# JAjchel_schemat.net
KiCad netlist of a schematic drawn in Altium Designer
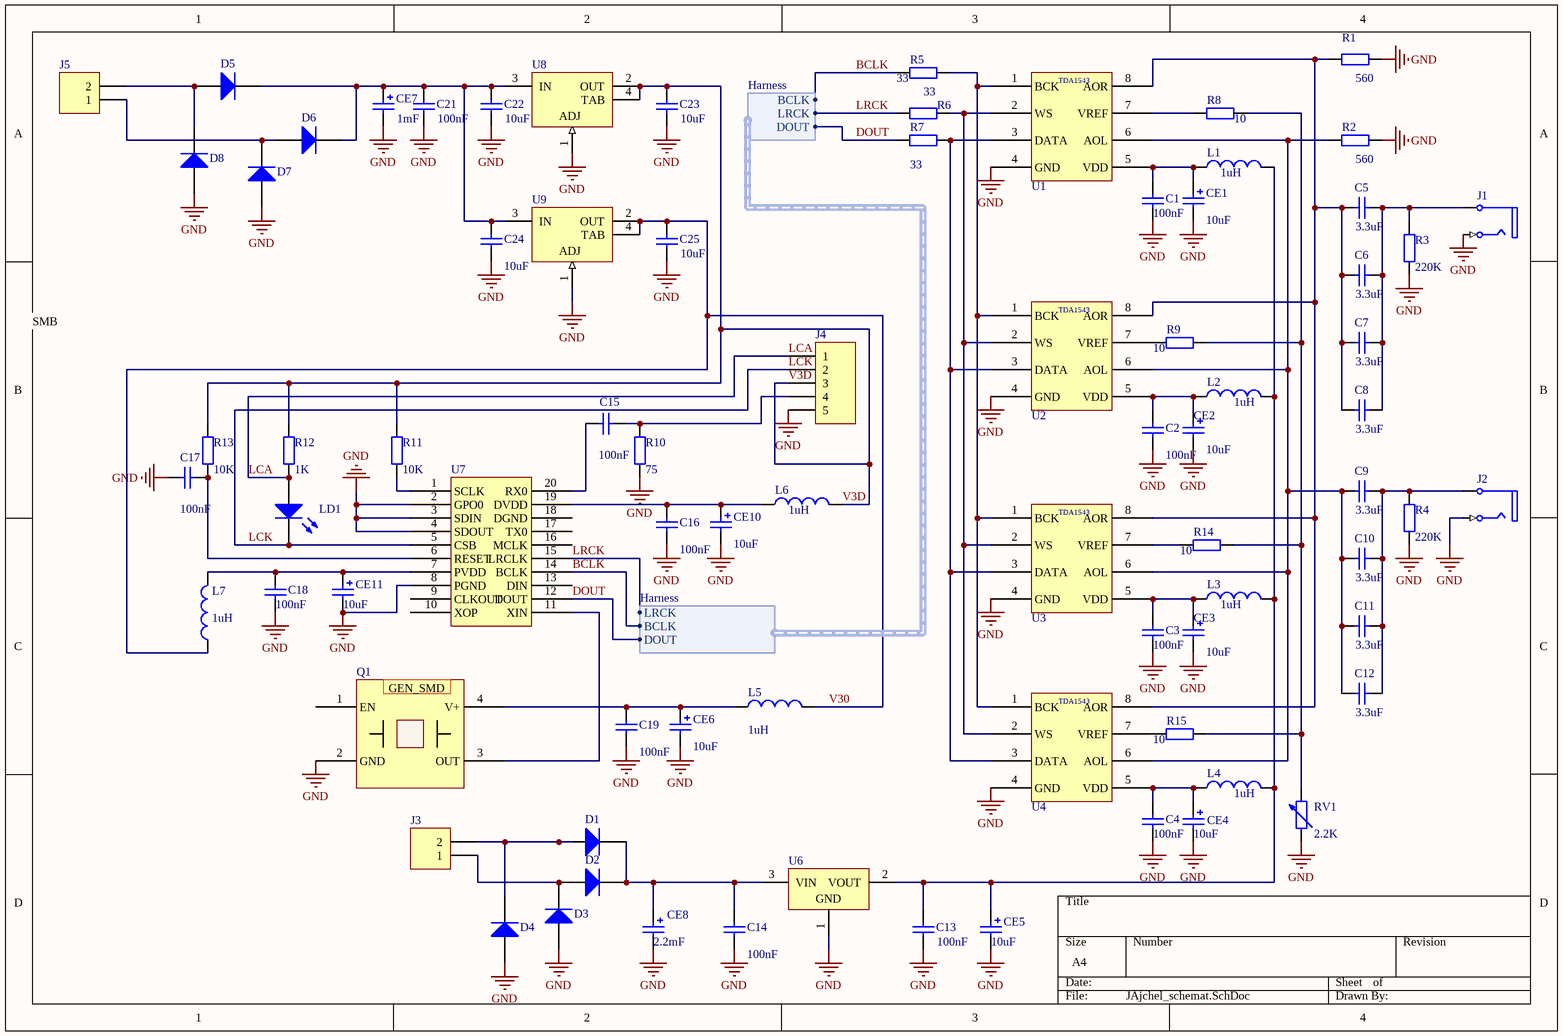
[diagram p0: JAjchel_schemat.SchDoc]

(export (version "E")
  (design (tool "Eeschema 10.0.6"))
  (components
    (comp (ref "C1")
      (value "100nF")
      (footprint "C1206")
      (description "Capacitor")
      (fields (field (name "Comment") "Comment") (field (name "PUBLISHER") "Altium Limited"))
      (libsource (lib "Miscellaneous Devices") (part "Cap"))
    )
    (comp (ref "C2")
      (value "100nF")
      (footprint "C1206")
      (description "Capacitor")
      (fields (field (name "Comment") "Comment") (field (name "PUBLISHER") "Altium Limited"))
      (libsource (lib "Miscellaneous Devices") (part "Cap"))
    )
    (comp (ref "C3")
      (value "100nF")
      (footprint "C1206")
      (description "Capacitor")
      (fields (field (name "Comment") "Comment") (field (name "PUBLISHER") "Altium Limited"))
      (libsource (lib "Miscellaneous Devices") (part "Cap"))
    )
    (comp (ref "C4")
      (value "100nF")
      (footprint "C1206")
      (description "Capacitor")
      (fields (field (name "Comment") "Comment") (field (name "PUBLISHER") "Altium Limited"))
      (libsource (lib "Miscellaneous Devices") (part "Cap"))
    )
    (comp (ref "C5")
      (value "3.3uF")
      (footprint "RAD-0.3")
      (description "Capacitor")
      (fields (field (name "Comment") "Comment") (field (name "PUBLISHER") "Altium Limited"))
      (libsource (lib "Miscellaneous Devices") (part "Cap"))
    )
    (comp (ref "C6")
      (value "3.3uF")
      (footprint "RAD-0.3")
      (description "Capacitor")
      (fields (field (name "Comment") "Comment") (field (name "PUBLISHER") "Altium Limited"))
      (libsource (lib "Miscellaneous Devices") (part "Cap"))
    )
    (comp (ref "C7")
      (value "3.3uF")
      (footprint "RAD-0.3")
      (description "Capacitor")
      (fields (field (name "Comment") "Comment") (field (name "PUBLISHER") "Altium Limited"))
      (libsource (lib "Miscellaneous Devices") (part "Cap"))
    )
    (comp (ref "C8")
      (value "3.3uF")
      (footprint "RAD-0.3")
      (description "Capacitor")
      (fields (field (name "Comment") "Comment") (field (name "PUBLISHER") "Altium Limited"))
      (libsource (lib "Miscellaneous Devices") (part "Cap"))
    )
    (comp (ref "C9")
      (value "3.3uF")
      (footprint "RAD-0.3")
      (description "Capacitor")
      (fields (field (name "Comment") "Comment") (field (name "PUBLISHER") "Altium Limited"))
      (libsource (lib "Miscellaneous Devices") (part "Cap"))
    )
    (comp (ref "C10")
      (value "3.3uF")
      (footprint "RAD-0.3")
      (description "Capacitor")
      (fields (field (name "Comment") "Comment") (field (name "PUBLISHER") "Altium Limited"))
      (libsource (lib "Miscellaneous Devices") (part "Cap"))
    )
    (comp (ref "C11")
      (value "3.3uF")
      (footprint "RAD-0.3")
      (description "Capacitor")
      (fields (field (name "Comment") "Comment") (field (name "PUBLISHER") "Altium Limited"))
      (libsource (lib "Miscellaneous Devices") (part "Cap"))
    )
    (comp (ref "C12")
      (value "3.3uF")
      (footprint "RAD-0.3")
      (description "Capacitor")
      (fields (field (name "Comment") "Comment") (field (name "PUBLISHER") "Altium Limited"))
      (libsource (lib "Miscellaneous Devices") (part "Cap"))
    )
    (comp (ref "C13")
      (value "100nF")
      (footprint "C1206")
      (description "Capacitor")
      (fields (field (name "Comment") "Comment") (field (name "PUBLISHER") "Altium Limited"))
      (libsource (lib "Miscellaneous Devices") (part "Cap"))
    )
    (comp (ref "C14")
      (value "100nF")
      (footprint "C1206")
      (description "Capacitor")
      (fields (field (name "Comment") "Comment") (field (name "PUBLISHER") "Altium Limited"))
      (libsource (lib "Miscellaneous Devices") (part "Cap"))
    )
    (comp (ref "C15")
      (value "100nF")
      (footprint "C1206")
      (description "Capacitor")
      (fields (field (name "Comment") "Comment") (field (name "PUBLISHER") "Altium Limited"))
      (libsource (lib "Miscellaneous Devices") (part "Cap"))
    )
    (comp (ref "C16")
      (value "100nF")
      (footprint "C1206")
      (description "Capacitor")
      (fields (field (name "Comment") "Comment") (field (name "PUBLISHER") "Altium Limited"))
      (libsource (lib "Miscellaneous Devices") (part "Cap"))
    )
    (comp (ref "C17")
      (value "100nF")
      (footprint "C1206")
      (description "Capacitor")
      (fields (field (name "Comment") "Comment") (field (name "PUBLISHER") "Altium Limited"))
      (libsource (lib "Miscellaneous Devices") (part "Cap"))
    )
    (comp (ref "C18")
      (value "100nF")
      (footprint "C1206")
      (description "Capacitor")
      (fields (field (name "Comment") "Comment") (field (name "PUBLISHER") "Altium Limited"))
      (libsource (lib "Miscellaneous Devices") (part "Cap"))
    )
    (comp (ref "C19")
      (value "100nF")
      (footprint "C1206")
      (description "Capacitor")
      (fields (field (name "Comment") "Comment") (field (name "PUBLISHER") "Altium Limited"))
      (libsource (lib "Miscellaneous Devices") (part "Cap"))
    )
    (comp (ref "C21")
      (value "100nF")
      (footprint "C1206")
      (description "Capacitor")
      (fields (field (name "Comment") "Comment") (field (name "PUBLISHER") "Altium Limited"))
      (libsource (lib "Miscellaneous Devices") (part "Cap"))
    )
    (comp (ref "C22")
      (value "10uF")
      (footprint "C1206")
      (description "Capacitor")
      (fields (field (name "Comment") "Comment") (field (name "PUBLISHER") "Altium Limited"))
      (libsource (lib "Miscellaneous Devices") (part "Cap"))
    )
    (comp (ref "C23")
      (value "10uF")
      (footprint "C1206")
      (description "Capacitor")
      (fields (field (name "Comment") "Comment") (field (name "PUBLISHER") "Altium Limited"))
      (libsource (lib "Miscellaneous Devices") (part "Cap"))
    )
    (comp (ref "C24")
      (value "10uF")
      (footprint "C1206")
      (description "Capacitor")
      (fields (field (name "Comment") "Comment") (field (name "PUBLISHER") "Altium Limited"))
      (libsource (lib "Miscellaneous Devices") (part "Cap"))
    )
    (comp (ref "C25")
      (value "10uF")
      (footprint "C1206")
      (description "Capacitor")
      (fields (field (name "Comment") "Comment") (field (name "PUBLISHER") "Altium Limited"))
      (libsource (lib "Miscellaneous Devices") (part "Cap"))
    )
    (comp (ref "CE1")
      (value "10uF")
      (footprint "C1206")
      (description "Polarized Capacitor (Axial)")
      (fields (field (name "Comment") "Comment") (field (name "PUBLISHER") "Altium Limited"))
      (libsource (lib "Miscellaneous Devices") (part "Cap Pol2"))
    )
    (comp (ref "CE2")
      (value "10uF")
      (footprint "C1206")
      (description "Polarized Capacitor (Axial)")
      (fields (field (name "Comment") "Comment") (field (name "PUBLISHER") "Altium Limited"))
      (libsource (lib "Miscellaneous Devices") (part "Cap Pol2"))
    )
    (comp (ref "CE3")
      (value "10uF")
      (footprint "C1206")
      (description "Polarized Capacitor (Axial)")
      (fields (field (name "Comment") "Comment") (field (name "PUBLISHER") "Altium Limited"))
      (libsource (lib "Miscellaneous Devices") (part "Cap Pol2"))
    )
    (comp (ref "CE4")
      (value "10uF")
      (footprint "C1206")
      (description "Polarized Capacitor (Axial)")
      (fields (field (name "Comment") "Comment") (field (name "PUBLISHER") "Altium Limited"))
      (libsource (lib "Miscellaneous Devices") (part "Cap Pol2"))
    )
    (comp (ref "CE5")
      (value "10uF")
      (footprint "C1206")
      (description "Polarized Capacitor (Axial)")
      (fields (field (name "Comment") "Comment") (field (name "PUBLISHER") "Altium Limited"))
      (libsource (lib "Miscellaneous Devices") (part "Cap Pol2"))
    )
    (comp (ref "CE6")
      (value "10uF")
      (footprint "C1206")
      (description "Polarized Capacitor (Axial)")
      (fields (field (name "Comment") "Comment") (field (name "PUBLISHER") "Altium Limited"))
      (libsource (lib "Miscellaneous Devices") (part "Cap Pol2"))
    )
    (comp (ref "CE7")
      (value "1mF")
      (footprint "POLAR0.8")
      (description "Polarized Capacitor (Axial)")
      (fields (field (name "Comment") "Comment") (field (name "PUBLISHER") "Altium Limited"))
      (libsource (lib "Miscellaneous Devices") (part "Cap Pol2"))
    )
    (comp (ref "CE8")
      (value "2.2mF")
      (footprint "POLAR0.8")
      (description "Polarized Capacitor (Axial)")
      (fields (field (name "Comment") "Comment") (field (name "PUBLISHER") "Altium Limited"))
      (libsource (lib "Miscellaneous Devices") (part "Cap Pol2"))
    )
    (comp (ref "CE10")
      (value "10uF")
      (footprint "C1206")
      (description "Polarized Capacitor (Axial)")
      (fields (field (name "Comment") "Comment") (field (name "PUBLISHER") "Altium Limited"))
      (libsource (lib "Miscellaneous Devices") (part "Cap Pol2"))
    )
    (comp (ref "CE11")
      (value "10uF")
      (footprint "C1206")
      (description "Polarized Capacitor (Axial)")
      (fields (field (name "Comment") "Comment") (field (name "PUBLISHER") "Altium Limited"))
      (libsource (lib "Miscellaneous Devices") (part "Cap Pol2"))
    )
    (comp (ref "D1") (value "Comment") (libsource (lib "D-AK-2") (part "D-AK-2")))
    (comp (ref "D2") (value "Comment") (libsource (lib "D-AK-2") (part "D-AK-2")))
    (comp (ref "D3") (value "Comment") (libsource (lib "D-AK-2") (part "D-AK-2")))
    (comp (ref "D4") (value "Comment") (libsource (lib "Altium Content Vault") (part "SYM-0080-00036-1")))
    (comp (ref "D5") (value "Comment") (libsource (lib "Altium Content Vault") (part "SYM-0080-00036-1")))
    (comp (ref "D6") (value "Comment") (libsource (lib "D-AK-2") (part "D-AK-2")))
    (comp (ref "D7") (value "Comment") (libsource (lib "D-AK-2") (part "D-AK-2")))
    (comp (ref "D8") (value "Comment") (libsource (lib "D-AK-2") (part "D-AK-2")))
    (comp (ref "J1")
      (value "Comment")
      (footprint "RCA/4.5-H2")
      (description "RCA Phono Jack, Right Angle, Thru-Hole, Snap-In")
      (fields (field (name "PUBLISHER") "Altium Limited"))
      (libsource (lib "Miscellaneous Connectors") (part "RCA"))
    )
    (comp (ref "J2")
      (value "Comment")
      (footprint "RCA/4.5-H2")
      (description "RCA Phono Jack, Right Angle, Thru-Hole, Snap-In")
      (fields (field (name "PUBLISHER") "Altium Limited"))
      (libsource (lib "Miscellaneous Connectors") (part "RCA"))
    )
    (comp (ref "J3")
      (value "Comment")
      (footprint "HDR1X2")
      (description "Header, 2-Pin")
      (fields (field (name "PUBLISHER") "Altium Limited"))
      (libsource (lib "Miscellaneous Connectors") (part "Header 2"))
    )
    (comp (ref "J4")
      (value "Comment")
      (footprint "HDR1X5")
      (description "Header, 5-Pin")
      (fields (field (name "PUBLISHER") "Altium Limited"))
      (libsource (lib "Miscellaneous Connectors") (part "Header 5"))
    )
    (comp (ref "J5")
      (value "Comment")
      (footprint "HDR1X2")
      (description "Header, 2-Pin")
      (fields (field (name "PUBLISHER") "Altium Limited"))
      (libsource (lib "Miscellaneous Connectors") (part "Header 2"))
    )
    (comp (ref "L1")
      (value "1uH")
      (footprint "0402-A")
      (description "Inductor")
      (fields (field (name "Comment") "Comment") (field (name "PUBLISHER") "Altium Limited"))
      (libsource (lib "Miscellaneous Devices") (part "Inductor"))
    )
    (comp (ref "L2")
      (value "1uH")
      (footprint "0402-A")
      (description "Inductor")
      (fields (field (name "Comment") "Comment") (field (name "PUBLISHER") "Altium Limited"))
      (libsource (lib "Miscellaneous Devices") (part "Inductor"))
    )
    (comp (ref "L3")
      (value "1uH")
      (footprint "0402-A")
      (description "Inductor")
      (fields (field (name "Comment") "Comment") (field (name "PUBLISHER") "Altium Limited"))
      (libsource (lib "Miscellaneous Devices") (part "Inductor"))
    )
    (comp (ref "L4")
      (value "1uH")
      (footprint "0402-A")
      (description "Inductor")
      (fields (field (name "Comment") "Comment") (field (name "PUBLISHER") "Altium Limited"))
      (libsource (lib "Miscellaneous Devices") (part "Inductor"))
    )
    (comp (ref "L5")
      (value "1uH")
      (footprint "0402-A")
      (description "Inductor")
      (fields (field (name "Comment") "Comment") (field (name "PUBLISHER") "Altium Limited"))
      (libsource (lib "Miscellaneous Devices") (part "Inductor"))
    )
    (comp (ref "L6")
      (value "1uH")
      (footprint "0402-A")
      (description "Inductor")
      (fields (field (name "Comment") "Comment") (field (name "PUBLISHER") "Altium Limited"))
      (libsource (lib "Miscellaneous Devices") (part "Inductor"))
    )
    (comp (ref "L7")
      (value "1uH")
      (footprint "0402-A")
      (description "Inductor")
      (fields (field (name "Comment") "Comment") (field (name "PUBLISHER") "Altium Limited"))
      (libsource (lib "Miscellaneous Devices") (part "Inductor"))
    )
    (comp (ref "LD1")
      (value "Comment")
      (footprint "LED-1")
      (description "Typical RED GaAs LED")
      (fields (field (name "PUBLISHER") "Altium Limited"))
      (libsource (lib "Miscellaneous Devices") (part "LED1"))
    )
    (comp (ref "Q1")
      (value "Comment")
      (description "Oscilator 12MHz")
      (libsource (lib "JAjchel_projekt") (part "Oscilator12mhz"))
    )
    (comp (ref "R1")
      (value "560")
      (footprint "J1-0603")
      (description "Resistor")
      (fields (field (name "Comment") "Comment") (field (name "PUBLISHER") "Altium Limited"))
      (libsource (lib "Miscellaneous Devices") (part "Res2"))
    )
    (comp (ref "R2")
      (value "560")
      (footprint "J1-0603")
      (description "Resistor")
      (fields (field (name "Comment") "Comment") (field (name "PUBLISHER") "Altium Limited"))
      (libsource (lib "Miscellaneous Devices") (part "Res2"))
    )
    (comp (ref "R3")
      (value "220K")
      (footprint "J1-0603")
      (description "Resistor")
      (fields (field (name "Comment") "Comment") (field (name "PUBLISHER") "Altium Limited"))
      (libsource (lib "") (part "Res2_1"))
    )
    (comp (ref "R4")
      (value "220K")
      (footprint "J1-0603")
      (description "Resistor")
      (fields (field (name "Comment") "Comment") (field (name "PUBLISHER") "Altium Limited"))
      (libsource (lib "") (part "Res2_1"))
    )
    (comp (ref "R5")
      (value "33")
      (footprint "J1-0603")
      (description "Resistor")
      (fields (field (name "Comment") "Comment") (field (name "PUBLISHER") "Altium Limited"))
      (libsource (lib "Miscellaneous Devices") (part "Res2"))
    )
    (comp (ref "R6")
      (value "33")
      (footprint "J1-0603")
      (description "Resistor")
      (fields (field (name "Comment") "Comment") (field (name "PUBLISHER") "Altium Limited"))
      (libsource (lib "Miscellaneous Devices") (part "Res2"))
    )
    (comp (ref "R7")
      (value "33")
      (footprint "J1-0603")
      (description "Resistor")
      (fields (field (name "Comment") "Comment") (field (name "PUBLISHER") "Altium Limited"))
      (libsource (lib "Miscellaneous Devices") (part "Res2"))
    )
    (comp (ref "R8")
      (value "10")
      (footprint "J1-0603")
      (description "Resistor")
      (fields (field (name "Comment") "Comment") (field (name "PUBLISHER") "Altium Limited"))
      (libsource (lib "Miscellaneous Devices") (part "Res2"))
    )
    (comp (ref "R9")
      (value "10")
      (footprint "J1-0603")
      (description "Resistor")
      (fields (field (name "Comment") "Comment") (field (name "PUBLISHER") "Altium Limited"))
      (libsource (lib "Miscellaneous Devices") (part "Res2"))
    )
    (comp (ref "R10")
      (value "75")
      (footprint "J1-0603")
      (description "Resistor")
      (fields (field (name "Comment") "Comment") (field (name "PUBLISHER") "Altium Limited"))
      (libsource (lib "") (part "Res2_1"))
    )
    (comp (ref "R11")
      (value "10K")
      (footprint "J1-0603")
      (description "Resistor")
      (fields (field (name "Comment") "Comment") (field (name "PUBLISHER") "Altium Limited"))
      (libsource (lib "") (part "Res2_1"))
    )
    (comp (ref "R12")
      (value "1K")
      (footprint "J1-0603")
      (description "Resistor")
      (fields (field (name "Comment") "Comment") (field (name "PUBLISHER") "Altium Limited"))
      (libsource (lib "") (part "Res2_1"))
    )
    (comp (ref "R13")
      (value "10K")
      (footprint "J1-0603")
      (description "Resistor")
      (fields (field (name "Comment") "Comment") (field (name "PUBLISHER") "Altium Limited"))
      (libsource (lib "") (part "Res2_1"))
    )
    (comp (ref "R14")
      (value "10")
      (footprint "J1-0603")
      (description "Resistor")
      (fields (field (name "Comment") "Comment") (field (name "PUBLISHER") "Altium Limited"))
      (libsource (lib "Miscellaneous Devices") (part "Res2"))
    )
    (comp (ref "R15")
      (value "10")
      (footprint "J1-0603")
      (description "Resistor")
      (fields (field (name "Comment") "Comment") (field (name "PUBLISHER") "Altium Limited"))
      (libsource (lib "Miscellaneous Devices") (part "Res2"))
    )
    (comp (ref "RV1")
      (value "2.2K")
      (footprint "AXIAL-0.6")
      (description "Variable Resistor")
      (fields (field (name "Comment") "Comment") (field (name "PUBLISHER") "Altium Limited"))
      (libsource (lib "Miscellaneous Devices") (part "Res Adj2"))
    )
    (comp (ref "U1") (value "Comment") (description "TDA1543") (libsource (lib "TDA1543") (part "TDA1543")))
    (comp (ref "U2") (value "Comment") (description "TDA1543") (libsource (lib "TDA1543") (part "TDA1543")))
    (comp (ref "U3") (value "Comment") (description "TDA1543") (libsource (lib "TDA1543") (part "TDA1543")))
    (comp (ref "U4") (value "Comment") (description "TDA1543") (libsource (lib "TDA1543") (part "TDA1543")))
    (comp (ref "U6") (value "Comment") (libsource (lib "LT-LT1086-T-3") (part "LT-LT1086-T-3")))
    (comp (ref "U7") (value "Comment") (libsource (lib "TDA1543") (part "WM8804")))
    (comp (ref "U8")
      (value "Comment")
      (libsource (lib "PM-REG-LM1086ADJ-SOT4") (part "PM-REG-LM1086ADJ-SOT4"))
    )
    (comp (ref "U9")
      (value "Comment")
      (libsource (lib "PM-REG-LM1086ADJ-SOT4") (part "PM-REG-LM1086ADJ-SOT4"))
    )
  )
  (nets
    (net (code "2") (name "/BCLK") (class "Default")
      (node (ref "R5") (pin "1") (pinfunction "1_1") (pintype "passive"))
      (node (ref "U7") (pin "14") (pinfunction "BCLK_14") (pintype "passive"))
    )
    (net (code "3") (name "/DOUT") (class "Default")
      (node (ref "R7") (pin "1") (pinfunction "1_1") (pintype "passive"))
      (node (ref "U7") (pin "12") (pinfunction "DOUT_12") (pintype "passive"))
    )
    (net (code "4") (name "/LCA") (class "Default")
      (node (ref "J4") (pin "1") (pinfunction "1_1") (pintype "passive"))
      (node (ref "LD1") (pin "1") (pinfunction "A_1") (pintype "passive"))
      (node (ref "R12") (pin "1") (pinfunction "1_1") (pintype "passive"))
    )
    (net (code "5") (name "/LCK") (class "Default")
      (node (ref "J4") (pin "2") (pinfunction "2_2") (pintype "passive"))
      (node (ref "LD1") (pin "2") (pinfunction "K_2") (pintype "passive"))
      (node (ref "U7") (pin "5") (pinfunction "CSB_5") (pintype "passive"))
    )
    (net (code "6") (name "/LRCK") (class "Default")
      (node (ref "R6") (pin "1") (pinfunction "1_1") (pintype "passive"))
      (node (ref "U7") (pin "15") (pinfunction "LRCLK_15") (pintype "passive"))
    )
    (net (code "7") (name "/V3D") (class "Default")
      (node (ref "C23") (pin "2") (pinfunction "2_2") (pintype "passive"))
      (node (ref "J4") (pin "3") (pinfunction "3_3") (pintype "passive"))
      (node (ref "L6") (pin "2") (pinfunction "2_2") (pintype "passive"))
      (node (ref "R11") (pin "2") (pinfunction "2_2") (pintype "passive"))
      (node (ref "R12") (pin "2") (pinfunction "2_2") (pintype "passive"))
      (node (ref "R13") (pin "2") (pinfunction "2_2") (pintype "passive"))
      (node (ref "U8") (pin "2") (pinfunction "OUT_2") (pintype "power_in"))
      (node (ref "U8") (pin "4") (pinfunction "TAB_4") (pintype "power_in"))
    )
    (net (code "8") (name "/V30") (class "Default")
      (node (ref "C25") (pin "2") (pinfunction "2_2") (pintype "passive"))
      (node (ref "L5") (pin "2") (pinfunction "2_2") (pintype "passive"))
      (node (ref "L7") (pin "1") (pinfunction "1_1") (pintype "passive"))
      (node (ref "U9") (pin "2") (pinfunction "OUT_2") (pintype "power_in"))
      (node (ref "U9") (pin "4") (pinfunction "TAB_4") (pintype "power_in"))
    )
    (net (code "10") (name "GND") (class "Default")
      (node (ref "C1") (pin "1") (pinfunction "1_1") (pintype "passive"))
      (node (ref "C13") (pin "1") (pinfunction "1_1") (pintype "passive"))
      (node (ref "C14") (pin "1") (pinfunction "1_1") (pintype "passive"))
      (node (ref "C16") (pin "1") (pinfunction "1_1") (pintype "passive"))
      (node (ref "C17") (pin "1") (pinfunction "1_1") (pintype "passive"))
      (node (ref "C18") (pin "1") (pinfunction "1_1") (pintype "passive"))
      (node (ref "C19") (pin "1") (pinfunction "1_1") (pintype "passive"))
      (node (ref "C2") (pin "1") (pinfunction "1_1") (pintype "passive"))
      (node (ref "C21") (pin "1") (pinfunction "1_1") (pintype "passive"))
      (node (ref "C22") (pin "1") (pinfunction "1_1") (pintype "passive"))
      (node (ref "C23") (pin "1") (pinfunction "1_1") (pintype "passive"))
      (node (ref "C24") (pin "1") (pinfunction "1_1") (pintype "passive"))
      (node (ref "C25") (pin "1") (pinfunction "1_1") (pintype "passive"))
      (node (ref "C3") (pin "1") (pinfunction "1_1") (pintype "passive"))
      (node (ref "C4") (pin "1") (pinfunction "1_1") (pintype "passive"))
      (node (ref "CE1") (pin "2") (pinfunction "2_2") (pintype "passive"))
      (node (ref "CE10") (pin "2") (pinfunction "2_2") (pintype "passive"))
      (node (ref "CE11") (pin "2") (pinfunction "2_2") (pintype "passive"))
      (node (ref "CE2") (pin "2") (pinfunction "2_2") (pintype "passive"))
      (node (ref "CE3") (pin "2") (pinfunction "2_2") (pintype "passive"))
      (node (ref "CE4") (pin "2") (pinfunction "2_2") (pintype "passive"))
      (node (ref "CE5") (pin "2") (pinfunction "2_2") (pintype "passive"))
      (node (ref "CE6") (pin "2") (pinfunction "2_2") (pintype "passive"))
      (node (ref "CE7") (pin "2") (pinfunction "2_2") (pintype "passive"))
      (node (ref "CE8") (pin "2") (pinfunction "2_2") (pintype "passive"))
      (node (ref "D3") (pin "1") (pinfunction "A_1") (pintype "passive"))
      (node (ref "D4") (pin "1") (pinfunction "A_1") (pintype "passive"))
      (node (ref "D7") (pin "1") (pinfunction "A_1") (pintype "passive"))
      (node (ref "D8") (pin "1") (pinfunction "A_1") (pintype "passive"))
      (node (ref "J1") (pin "2B") (pinfunction "Signal_2B") (pintype "input"))
      (node (ref "J2") (pin "2B") (pinfunction "Signal_2B") (pintype "input"))
      (node (ref "J4") (pin "5") (pinfunction "5_5") (pintype "passive"))
      (node (ref "Q1") (pin "2") (pinfunction "GND_2") (pintype "passive"))
      (node (ref "R1") (pin "2") (pinfunction "2_2") (pintype "passive"))
      (node (ref "R10") (pin "1") (pinfunction "1_1") (pintype "passive"))
      (node (ref "R2") (pin "2") (pinfunction "2_2") (pintype "passive"))
      (node (ref "R3") (pin "1") (pinfunction "1_1") (pintype "passive"))
      (node (ref "R4") (pin "1") (pinfunction "1_1") (pintype "passive"))
      (node (ref "RV1") (pin "1") (pinfunction "1_1") (pintype "passive"))
      (node (ref "U1") (pin "4") (pinfunction "GND_4") (pintype "passive"))
      (node (ref "U2") (pin "4") (pinfunction "GND_4") (pintype "passive"))
      (node (ref "U3") (pin "4") (pinfunction "GND_4") (pintype "passive"))
      (node (ref "U4") (pin "4") (pinfunction "GND_4") (pintype "passive"))
      (node (ref "U6") (pin "1") (pinfunction "GND_1") (pintype "power_in"))
      (node (ref "U7") (pin "2") (pinfunction "GPO0_2") (pintype "passive"))
      (node (ref "U7") (pin "3") (pinfunction "SDIN_3") (pintype "passive"))
      (node (ref "U7") (pin "4") (pinfunction "SDOUT_4") (pintype "passive"))
      (node (ref "U7") (pin "8") (pinfunction "PGND_8") (pintype "passive"))
      (node (ref "U8") (pin "1") (pinfunction "ADJ_1") (pintype "input"))
      (node (ref "U9") (pin "1") (pinfunction "ADJ_1") (pintype "input"))
    )
    (net (code "11") (name "Net-(C15-Pad2)") (class "Default")
      (node (ref "C15") (pin "2") (pinfunction "2_2") (pintype "passive"))
      (node (ref "J4") (pin "4") (pinfunction "4_4") (pintype "passive"))
      (node (ref "R10") (pin "2") (pinfunction "2_2") (pintype "passive"))
    )
    (net (code "12") (name "Net-(D1-A)") (class "Default")
      (node (ref "D1") (pin "1") (pinfunction "A_1") (pintype "passive"))
      (node (ref "D4") (pin "2") (pinfunction "K_2") (pintype "passive"))
      (node (ref "J3") (pin "2") (pinfunction "2_2") (pintype "passive"))
    )
    (net (code "13") (name "Net-(D1-K)") (class "Default")
      (node (ref "C14") (pin "2") (pinfunction "2_2") (pintype "passive"))
      (node (ref "CE8") (pin "1") (pinfunction "1_1") (pintype "passive"))
      (node (ref "D1") (pin "2") (pinfunction "K_2") (pintype "passive"))
      (node (ref "D2") (pin "2") (pinfunction "K_2") (pintype "passive"))
      (node (ref "U6") (pin "3") (pinfunction "VIN_3") (pintype "power_in"))
    )
    (net (code "14") (name "Net-(D2-A)") (class "Default")
      (node (ref "D2") (pin "1") (pinfunction "A_1") (pintype "passive"))
      (node (ref "D3") (pin "2") (pinfunction "K_2") (pintype "passive"))
      (node (ref "J3") (pin "1") (pinfunction "1_1") (pintype "passive"))
    )
    (net (code "15") (name "Net-(D5-A)") (class "Default")
      (node (ref "D5") (pin "1") (pinfunction "A_1") (pintype "passive"))
      (node (ref "D8") (pin "2") (pinfunction "K_2") (pintype "passive"))
      (node (ref "J5") (pin "2") (pinfunction "2_2") (pintype "passive"))
    )
    (net (code "16") (name "Net-(D5-K)") (class "Default")
      (node (ref "C21") (pin "2") (pinfunction "2_2") (pintype "passive"))
      (node (ref "C22") (pin "2") (pinfunction "2_2") (pintype "passive"))
      (node (ref "C24") (pin "2") (pinfunction "2_2") (pintype "passive"))
      (node (ref "CE7") (pin "1") (pinfunction "1_1") (pintype "passive"))
      (node (ref "D5") (pin "2") (pinfunction "K_2") (pintype "passive"))
      (node (ref "D6") (pin "2") (pinfunction "K_2") (pintype "passive"))
      (node (ref "U8") (pin "3") (pinfunction "IN_3") (pintype "power_in"))
      (node (ref "U9") (pin "3") (pinfunction "IN_3") (pintype "power_in"))
    )
    (net (code "17") (name "Net-(D6-A)") (class "Default")
      (node (ref "D6") (pin "1") (pinfunction "A_1") (pintype "passive"))
      (node (ref "D7") (pin "2") (pinfunction "K_2") (pintype "passive"))
      (node (ref "J5") (pin "1") (pinfunction "1_1") (pintype "passive"))
    )
    (net (code "18") (name "Net-(J1-Ground)") (class "Default")
      (node (ref "C5") (pin "2") (pinfunction "2_2") (pintype "passive"))
      (node (ref "C6") (pin "2") (pinfunction "2_2") (pintype "passive"))
      (node (ref "C7") (pin "2") (pinfunction "2_2") (pintype "passive"))
      (node (ref "C8") (pin "2") (pinfunction "2_2") (pintype "passive"))
      (node (ref "J1") (pin "1A") (pinfunction "Ground_1A") (pintype "power_in"))
      (node (ref "R3") (pin "2") (pinfunction "2_2") (pintype "passive"))
    )
    (net (code "19") (name "Net-(J2-Ground)") (class "Default")
      (node (ref "C10") (pin "2") (pinfunction "2_2") (pintype "passive"))
      (node (ref "C11") (pin "2") (pinfunction "2_2") (pintype "passive"))
      (node (ref "C12") (pin "2") (pinfunction "2_2") (pintype "passive"))
      (node (ref "C9") (pin "2") (pinfunction "2_2") (pintype "passive"))
      (node (ref "J2") (pin "1A") (pinfunction "Ground_1A") (pintype "power_in"))
      (node (ref "R4") (pin "2") (pinfunction "2_2") (pintype "passive"))
    )
    (net (code "20") (name "Net-(Q1-OUT)") (class "Default")
      (node (ref "Q1") (pin "3") (pinfunction "OUT_3") (pintype "passive"))
      (node (ref "U7") (pin "11") (pinfunction "XIN_11") (pintype "passive"))
    )
    (net (code "21") (name "Net-(Q1-V+)") (class "Default")
      (node (ref "C19") (pin "2") (pinfunction "2_2") (pintype "passive"))
      (node (ref "CE6") (pin "1") (pinfunction "1_1") (pintype "passive"))
      (node (ref "L5") (pin "1") (pinfunction "1_1") (pintype "passive"))
      (node (ref "Q1") (pin "4") (pinfunction "V+_4") (pintype "passive"))
    )
    (net (code "22") (name "Net-(R14-Pad2)") (class "Default")
      (node (ref "R14") (pin "2") (pinfunction "2_2") (pintype "passive"))
      (node (ref "R15") (pin "2") (pinfunction "2_2") (pintype "passive"))
      (node (ref "R8") (pin "2") (pinfunction "2_2") (pintype "passive"))
      (node (ref "R9") (pin "2") (pinfunction "2_2") (pintype "passive"))
      (node (ref "RV1") (pin "2") (pinfunction "2_2") (pintype "passive"))
    )
    (net (code "23") (name "Net-(U1-AOL)") (class "Default")
      (node (ref "C10") (pin "1") (pinfunction "1_1") (pintype "passive"))
      (node (ref "C11") (pin "1") (pinfunction "1_1") (pintype "passive"))
      (node (ref "C12") (pin "1") (pinfunction "1_1") (pintype "passive"))
      (node (ref "C9") (pin "1") (pinfunction "1_1") (pintype "passive"))
      (node (ref "R2") (pin "1") (pinfunction "1_1") (pintype "passive"))
      (node (ref "U1") (pin "6") (pinfunction "AOL_6") (pintype "passive"))
      (node (ref "U2") (pin "6") (pinfunction "AOL_6") (pintype "passive"))
      (node (ref "U3") (pin "6") (pinfunction "AOL_6") (pintype "passive"))
      (node (ref "U4") (pin "6") (pinfunction "AOL_6") (pintype "passive"))
    )
    (net (code "24") (name "Net-(U1-AOR)") (class "Default")
      (node (ref "C5") (pin "1") (pinfunction "1_1") (pintype "passive"))
      (node (ref "C6") (pin "1") (pinfunction "1_1") (pintype "passive"))
      (node (ref "C7") (pin "1") (pinfunction "1_1") (pintype "passive"))
      (node (ref "C8") (pin "1") (pinfunction "1_1") (pintype "passive"))
      (node (ref "R1") (pin "1") (pinfunction "1_1") (pintype "passive"))
      (node (ref "U1") (pin "8") (pinfunction "AOR_8") (pintype "passive"))
      (node (ref "U2") (pin "8") (pinfunction "AOR_8") (pintype "passive"))
      (node (ref "U3") (pin "8") (pinfunction "AOR_8") (pintype "passive"))
      (node (ref "U4") (pin "8") (pinfunction "AOR_8") (pintype "passive"))
    )
    (net (code "25") (name "Net-(U1-BCK)") (class "Default")
      (node (ref "R5") (pin "2") (pinfunction "2_2") (pintype "passive"))
      (node (ref "U1") (pin "1") (pinfunction "BCK_1") (pintype "passive"))
      (node (ref "U2") (pin "1") (pinfunction "BCK_1") (pintype "passive"))
      (node (ref "U3") (pin "1") (pinfunction "BCK_1") (pintype "passive"))
      (node (ref "U4") (pin "1") (pinfunction "BCK_1") (pintype "passive"))
    )
    (net (code "26") (name "Net-(U1-DATA)") (class "Default")
      (node (ref "R7") (pin "2") (pinfunction "2_2") (pintype "passive"))
      (node (ref "U1") (pin "3") (pinfunction "DATA_3") (pintype "passive"))
      (node (ref "U2") (pin "3") (pinfunction "DATA_3") (pintype "passive"))
      (node (ref "U3") (pin "3") (pinfunction "DATA_3") (pintype "passive"))
      (node (ref "U4") (pin "3") (pinfunction "DATA_3") (pintype "passive"))
    )
    (net (code "27") (name "Net-(U1-VDD)") (class "Default")
      (node (ref "C1") (pin "2") (pinfunction "2_2") (pintype "passive"))
      (node (ref "CE1") (pin "1") (pinfunction "1_1") (pintype "passive"))
      (node (ref "L1") (pin "1") (pinfunction "1_1") (pintype "passive"))
      (node (ref "U1") (pin "5") (pinfunction "VDD_5") (pintype "passive"))
    )
    (net (code "28") (name "Net-(U1-VREF)") (class "Default")
      (node (ref "R8") (pin "1") (pinfunction "1_1") (pintype "passive"))
      (node (ref "U1") (pin "7") (pinfunction "VREF_7") (pintype "passive"))
    )
    (net (code "29") (name "Net-(U1-WS)") (class "Default")
      (node (ref "R6") (pin "2") (pinfunction "2_2") (pintype "passive"))
      (node (ref "U1") (pin "2") (pinfunction "WS_2") (pintype "passive"))
      (node (ref "U2") (pin "2") (pinfunction "WS_2") (pintype "passive"))
      (node (ref "U3") (pin "2") (pinfunction "WS_2") (pintype "passive"))
      (node (ref "U4") (pin "2") (pinfunction "WS_2") (pintype "passive"))
    )
    (net (code "30") (name "Net-(U2-VDD)") (class "Default")
      (node (ref "C2") (pin "2") (pinfunction "2_2") (pintype "passive"))
      (node (ref "CE2") (pin "1") (pinfunction "1_1") (pintype "passive"))
      (node (ref "L2") (pin "1") (pinfunction "1_1") (pintype "passive"))
      (node (ref "U2") (pin "5") (pinfunction "VDD_5") (pintype "passive"))
    )
    (net (code "31") (name "Net-(U2-VREF)") (class "Default")
      (node (ref "R9") (pin "1") (pinfunction "1_1") (pintype "passive"))
      (node (ref "U2") (pin "7") (pinfunction "VREF_7") (pintype "passive"))
    )
    (net (code "32") (name "Net-(U3-VDD)") (class "Default")
      (node (ref "C3") (pin "2") (pinfunction "2_2") (pintype "passive"))
      (node (ref "CE3") (pin "1") (pinfunction "1_1") (pintype "passive"))
      (node (ref "L3") (pin "1") (pinfunction "1_1") (pintype "passive"))
      (node (ref "U3") (pin "5") (pinfunction "VDD_5") (pintype "passive"))
    )
    (net (code "33") (name "Net-(U3-VREF)") (class "Default")
      (node (ref "R14") (pin "1") (pinfunction "1_1") (pintype "passive"))
      (node (ref "U3") (pin "7") (pinfunction "VREF_7") (pintype "passive"))
    )
    (net (code "34") (name "Net-(U4-VDD)") (class "Default")
      (node (ref "C4") (pin "2") (pinfunction "2_2") (pintype "passive"))
      (node (ref "CE4") (pin "1") (pinfunction "1_1") (pintype "passive"))
      (node (ref "L4") (pin "1") (pinfunction "1_1") (pintype "passive"))
      (node (ref "U4") (pin "5") (pinfunction "VDD_5") (pintype "passive"))
    )
    (net (code "35") (name "Net-(U4-VREF)") (class "Default")
      (node (ref "R15") (pin "1") (pinfunction "1_1") (pintype "passive"))
      (node (ref "U4") (pin "7") (pinfunction "VREF_7") (pintype "passive"))
    )
    (net (code "36") (name "Net-(U6-VOUT)") (class "Default")
      (node (ref "C13") (pin "2") (pinfunction "2_2") (pintype "passive"))
      (node (ref "CE5") (pin "1") (pinfunction "1_1") (pintype "passive"))
      (node (ref "L1") (pin "2") (pinfunction "2_2") (pintype "passive"))
      (node (ref "L2") (pin "2") (pinfunction "2_2") (pintype "passive"))
      (node (ref "L3") (pin "2") (pinfunction "2_2") (pintype "passive"))
      (node (ref "L4") (pin "2") (pinfunction "2_2") (pintype "passive"))
      (node (ref "U6") (pin "2") (pinfunction "VOUT_2") (pintype "power_in"))
    )
    (net (code "37") (name "Net-(U7-DVDD)") (class "Default")
      (node (ref "C16") (pin "2") (pinfunction "2_2") (pintype "passive"))
      (node (ref "CE10") (pin "1") (pinfunction "1_1") (pintype "passive"))
      (node (ref "L6") (pin "1") (pinfunction "1_1") (pintype "passive"))
      (node (ref "U7") (pin "19") (pinfunction "DVDD_19") (pintype "passive"))
    )
    (net (code "38") (name "Net-(U7-PVDD)") (class "Default")
      (node (ref "C18") (pin "2") (pinfunction "2_2") (pintype "passive"))
      (node (ref "CE11") (pin "1") (pinfunction "1_1") (pintype "passive"))
      (node (ref "L7") (pin "2") (pinfunction "2_2") (pintype "passive"))
      (node (ref "U7") (pin "7") (pinfunction "PVDD_7") (pintype "passive"))
    )
    (net (code "39") (name "Net-(U7-RESET)") (class "Default")
      (node (ref "C17") (pin "2") (pinfunction "2_2") (pintype "passive"))
      (node (ref "R13") (pin "1") (pinfunction "1_1") (pintype "passive"))
      (node (ref "U7") (pin "6") (pinfunction "RESET_6") (pintype "passive"))
    )
    (net (code "40") (name "Net-(U7-RX0)") (class "Default")
      (node (ref "C15") (pin "1") (pinfunction "1_1") (pintype "passive"))
      (node (ref "U7") (pin "20") (pinfunction "RX0_20") (pintype "passive"))
    )
    (net (code "41") (name "Net-(U7-SCLK)") (class "Default")
      (node (ref "R11") (pin "1") (pinfunction "1_1") (pintype "passive"))
      (node (ref "U7") (pin "1") (pinfunction "SCLK_1") (pintype "passive"))
    )
    (net (code "42") (name "unconnected-(Q1-EN-Pad1)") (class "Default")
      (node (ref "Q1") (pin "1") (pinfunction "EN_1") (pintype "passive"))
    )
    (net (code "43") (name "unconnected-(U7-CLKOUT-Pad9)") (class "Default")
      (node (ref "U7") (pin "9") (pinfunction "CLKOUT_9") (pintype "passive"))
    )
    (net (code "44") (name "unconnected-(U7-DGND-Pad18)") (class "Default")
      (node (ref "U7") (pin "18") (pinfunction "DGND_18") (pintype "passive"))
    )
    (net (code "45") (name "unconnected-(U7-DIN-Pad13)") (class "Default")
      (node (ref "U7") (pin "13") (pinfunction "DIN_13") (pintype "passive"))
    )
    (net (code "46") (name "unconnected-(U7-MCLK-Pad16)") (class "Default")
      (node (ref "U7") (pin "16") (pinfunction "MCLK_16") (pintype "passive"))
    )
    (net (code "47") (name "unconnected-(U7-TX0-Pad17)") (class "Default")
      (node (ref "U7") (pin "17") (pinfunction "TX0_17") (pintype "passive"))
    )
    (net (code "48") (name "unconnected-(U7-XOP-Pad10)") (class "Default")
      (node (ref "U7") (pin "10") (pinfunction "XOP_10") (pintype "passive"))
    )
  )
)
